# Regulators.net
KiCad netlist of a schematic drawn in Altium Designer
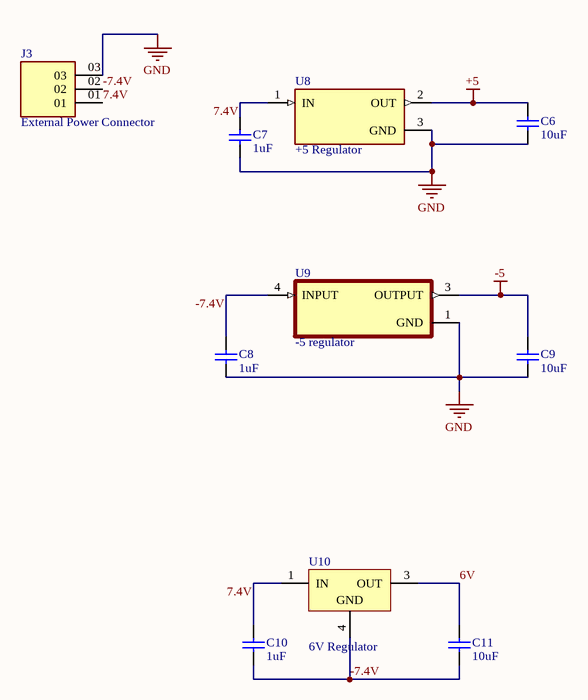
[diagram p0: Regulators.SchDoc]

(export (version "E")
  (design (tool "Eeschema 10.0.6"))
  (components
    (comp (ref "C6")
      (value "10uF")
      (footprint "CAPC2013X135X45ML10T25")
      (description "GRM21BR60J106KE19L")
      (fields (field (name "MANUFACTURER") "Murata"))
      (libsource (lib "Capacitors") (part "10uF"))
    )
    (comp (ref "C7")
      (value "1uF")
      (footprint "CAPC2013X135X45ML10T25")
      (fields (field (name "MANUFACTURER") "Murata"))
      (libsource (lib "Capacitors") (part "1uF"))
    )
    (comp (ref "C8")
      (value "1uF")
      (footprint "CAPC2013X135X45ML10T25")
      (fields (field (name "MANUFACTURER") "Murata"))
      (libsource (lib "Capacitors") (part "1uF"))
    )
    (comp (ref "C9")
      (value "10uF")
      (footprint "CAPC2013X135X45ML10T25")
      (description "GRM21BR60J106KE19L")
      (fields (field (name "MANUFACTURER") "Murata"))
      (libsource (lib "Capacitors") (part "10uF"))
    )
    (comp (ref "C10")
      (value "1uF")
      (footprint "CAPC2013X135X45ML10T25")
      (fields (field (name "MANUFACTURER") "Murata"))
      (libsource (lib "Capacitors") (part "1uF"))
    )
    (comp (ref "C11")
      (value "10uF")
      (footprint "CAPC2013X135X45ML10T25")
      (description "GRM21BR60J106KE19L")
      (fields (field (name "MANUFACTURER") "Murata"))
      (libsource (lib "Capacitors") (part "10uF"))
    )
    (comp (ref "J3")
      (value "External Power Connector")
      (footprint "SAMTEC_HTSW-103-XX-X-S")
      (description "HTSW-103-XX-X-S")
      (fields (field (name "MF") "Samtec"))
      (libsource (lib "3 pin connector") (part "HTSW-103-XX-X-S"))
    )
    (comp (ref "U8")
      (value "+5 Regulator")
      (footprint "TO254P1542X460-3N")
      (description "Linear Voltage Regulator IC Positive Fixed 1 Output 1.5A D2PAK")
      (fields (field (name "MF") "STMicroelectronics") (field (name "MP") "L7805CD2T-TR"))
      (libsource (lib "5 positive regulator") (part "L7805CD2T-TR"))
    )
    (comp (ref "U9")
      (value "-5 regulator")
      (footprint "VREG_L7805ACD2T")
      (description "Linear Voltage Regulator IC Negative Fixed 1 Output 1.5A D2PAK")
      (fields (field (name "MF") "STMicroelectronics") (field (name "MP") "L7905CD2T-TR"))
      (libsource (lib "5 negative regulator") (part "L7905CD2T-TR"))
    )
    (comp (ref "U10")
      (value "6V Regulator")
      (footprint "TO-263_L")
      (description "Positive Voltage Regulator, 3-Pin D2PAK, Tape and Reel; L7806CD2T-TR")
      (libsource (lib "Other") (part "6V Regulator"))
    )
  )
  (nets
    (net (code "1") (name "+5") (class "Default")
      (node (ref "C6") (pin "2") (pinfunction "2_2") (pintype "passive"))
      (node (ref "U8") (pin "2") (pinfunction "OUT_2") (pintype "output"))
    )
    (net (code "2") (name "-5") (class "Default")
      (node (ref "C9") (pin "2") (pinfunction "2_2") (pintype "passive"))
      (node (ref "U9") (pin "3") (pinfunction "OUTPUT_3") (pintype "output"))
    )
    (net (code "3") (name "/-7.4V") (class "Default")
      (node (ref "C10") (pin "1") (pinfunction "1_1") (pintype "passive"))
      (node (ref "C11") (pin "1") (pinfunction "1_1") (pintype "passive"))
      (node (ref "C8") (pin "2") (pinfunction "2_2") (pintype "passive"))
      (node (ref "J3") (pin "02") (pinfunction "02_02") (pintype "passive"))
      (node (ref "U10") (pin "4") (pinfunction "GND_4") (pintype "power_in"))
      (node (ref "U9") (pin "4") (pinfunction "INPUT_4") (pintype "input"))
    )
    (net (code "4") (name "/6V") (class "Default")
      (node (ref "C11") (pin "2") (pinfunction "2_2") (pintype "passive"))
      (node (ref "U10") (pin "3") (pinfunction "OUT_3") (pintype "power_in"))
    )
    (net (code "5") (name "/7.4V") (class "Default")
      (node (ref "C10") (pin "2") (pinfunction "2_2") (pintype "passive"))
      (node (ref "C7") (pin "2") (pinfunction "2_2") (pintype "passive"))
      (node (ref "J3") (pin "01") (pinfunction "01_01") (pintype "passive"))
      (node (ref "U10") (pin "1") (pinfunction "IN_1") (pintype "power_in"))
      (node (ref "U8") (pin "1") (pinfunction "IN_1") (pintype "input"))
    )
    (net (code "6") (name "GND") (class "Default")
      (node (ref "C6") (pin "1") (pinfunction "1_1") (pintype "passive"))
      (node (ref "C7") (pin "1") (pinfunction "1_1") (pintype "passive"))
      (node (ref "C8") (pin "1") (pinfunction "1_1") (pintype "passive"))
      (node (ref "C9") (pin "1") (pinfunction "1_1") (pintype "passive"))
      (node (ref "J3") (pin "03") (pinfunction "03_03") (pintype "passive"))
      (node (ref "U8") (pin "3") (pinfunction "GND_3") (pintype "power_in"))
      (node (ref "U9") (pin "1") (pinfunction "GND_1") (pintype "power_in"))
    )
  )
)
